# PIN2DMD_PWR.net
KiCad netlist of a schematic drawn in EAGLE
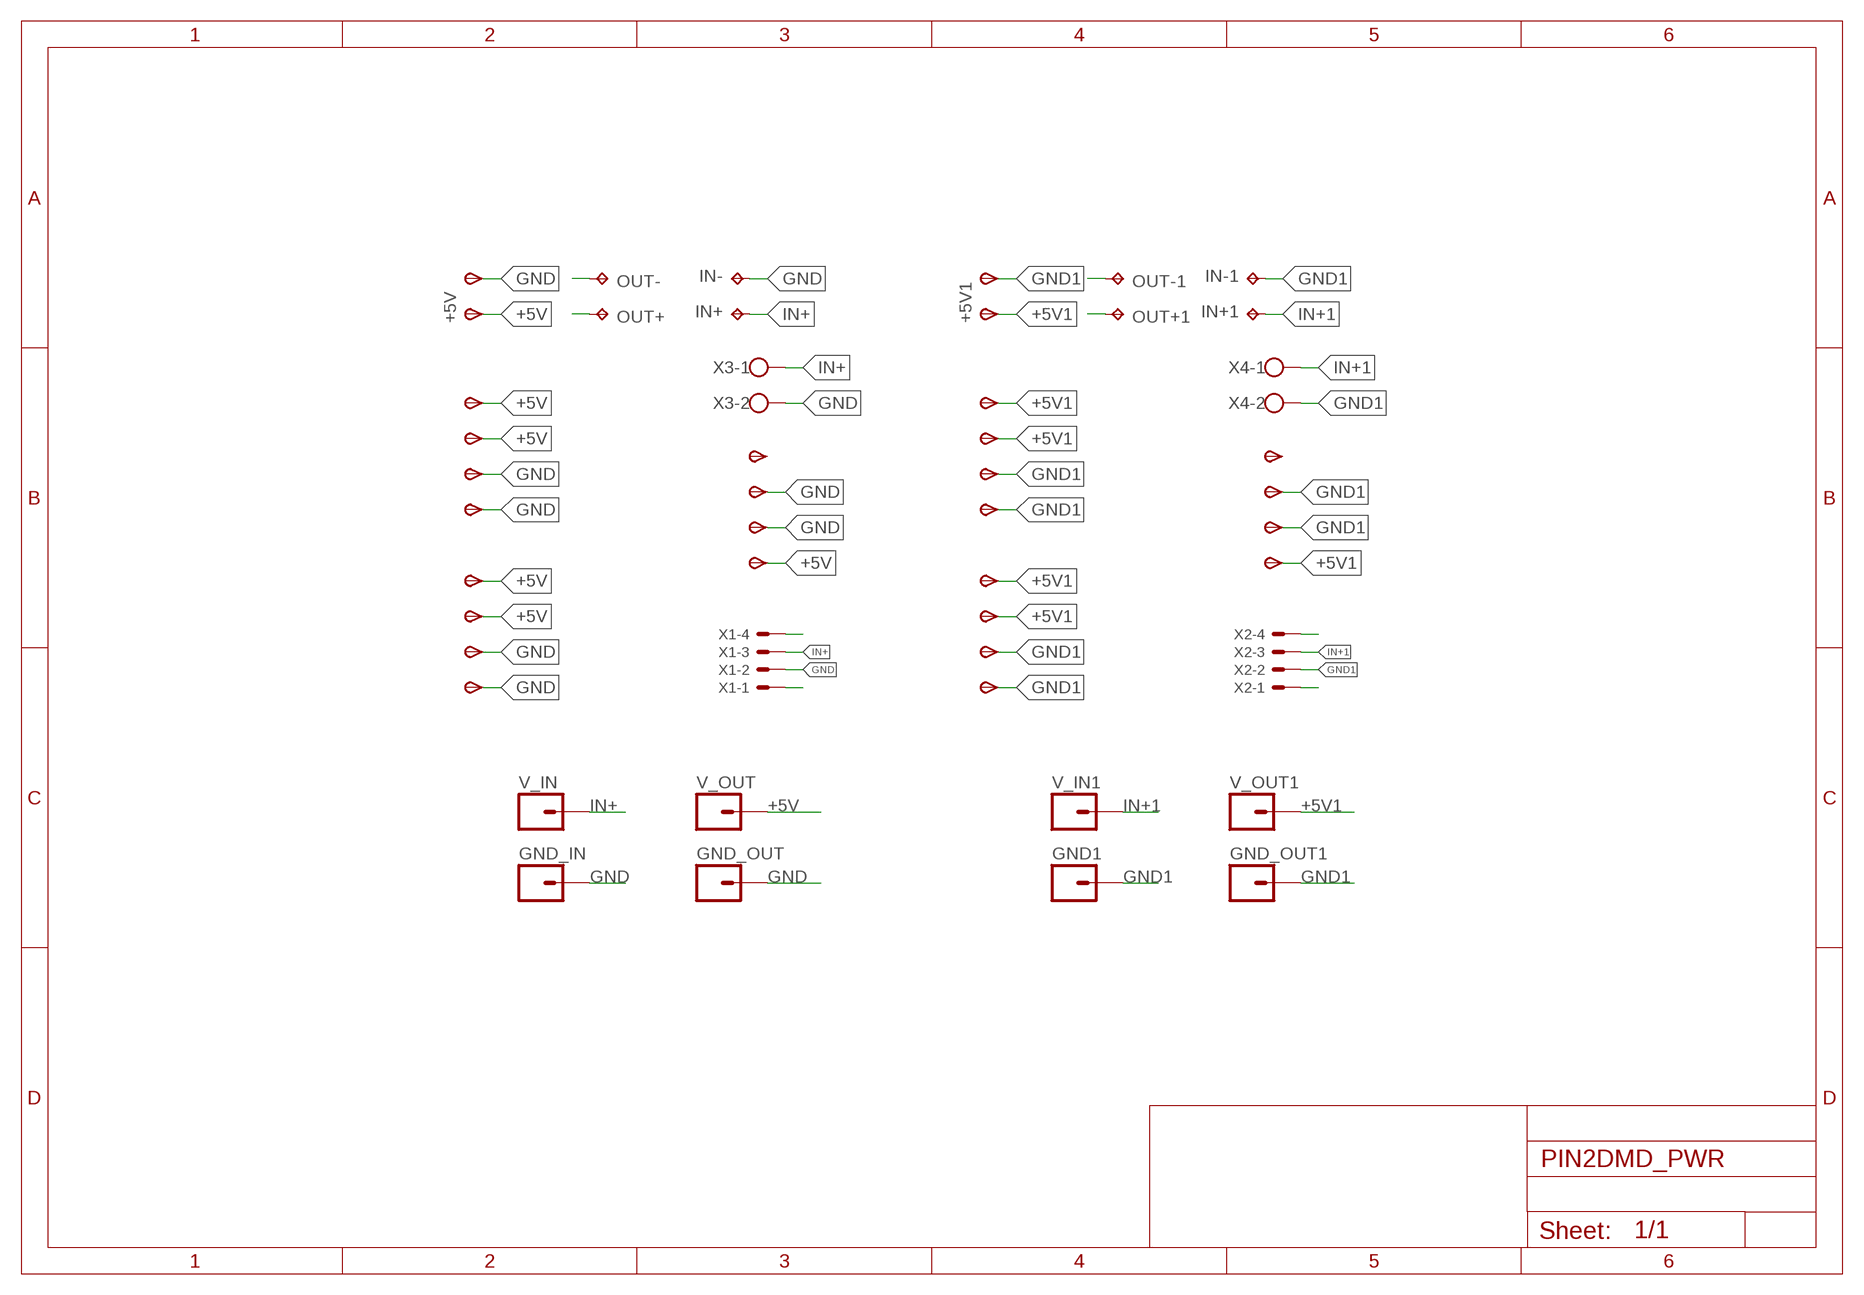
[diagram p0: schematic, sheet 1]

(export (version "E")
  (design (tool "Eeschema 10.0.6"))
  (components
    (comp (ref "+5V")
      (value "TPSPAD1-20Y")
      (footprint "eagle-import:P1-20Y")
      (libsource (lib "eagle-import") (part "TPSPAD1-20Y"))
    )
    (comp (ref "+5V1")
      (value "TPSPAD1-20Y")
      (footprint "eagle-import:P1-20Y")
      (libsource (lib "eagle-import") (part "TPSPAD1-20Y"))
    )
    (comp (ref "GND1")
      (value "M01PTH")
      (footprint "eagle-import:1X01")
      (libsource (lib "eagle-import") (part "M01PTH"))
    )
    (comp (ref "GND_IN")
      (value "M01PTH")
      (footprint "eagle-import:1X01")
      (libsource (lib "eagle-import") (part "M01PTH"))
    )
    (comp (ref "GND_OUT")
      (value "M01PTH")
      (footprint "eagle-import:1X01")
      (libsource (lib "eagle-import") (part "M01PTH"))
    )
    (comp (ref "GND_OUT1")
      (value "M01PTH")
      (footprint "eagle-import:1X01")
      (libsource (lib "eagle-import") (part "M01PTH"))
    )
    (comp (ref "IN+")
      (value "TPPAD1-20")
      (footprint "eagle-import:P1-20")
      (libsource (lib "eagle-import") (part "TPPAD1-20"))
    )
    (comp (ref "IN+1")
      (value "TPPAD1-20")
      (footprint "eagle-import:P1-20")
      (libsource (lib "eagle-import") (part "TPPAD1-20"))
    )
    (comp (ref "IN-")
      (value "TPPAD1-20")
      (footprint "eagle-import:P1-20")
      (libsource (lib "eagle-import") (part "TPPAD1-20"))
    )
    (comp (ref "IN-1")
      (value "TPPAD1-20")
      (footprint "eagle-import:P1-20")
      (libsource (lib "eagle-import") (part "TPPAD1-20"))
    )
    (comp (ref "OUT+")
      (value "TPPAD1-20")
      (footprint "eagle-import:P1-20")
      (libsource (lib "eagle-import") (part "TPPAD1-20"))
    )
    (comp (ref "OUT+1")
      (value "TPPAD1-20")
      (footprint "eagle-import:P1-20")
      (libsource (lib "eagle-import") (part "TPPAD1-20"))
    )
    (comp (ref "OUT-")
      (value "TPPAD1-20")
      (footprint "eagle-import:P1-20")
      (libsource (lib "eagle-import") (part "TPPAD1-20"))
    )
    (comp (ref "OUT-1")
      (value "TPPAD1-20")
      (footprint "eagle-import:P1-20")
      (libsource (lib "eagle-import") (part "TPPAD1-20"))
    )
    (comp (ref "TP1")
      (value "TPSPAD1-20Y")
      (footprint "eagle-import:P1-20Y")
      (libsource (lib "eagle-import") (part "TPSPAD1-20Y"))
    )
    (comp (ref "TP2")
      (value "TPSPAD1-20Y")
      (footprint "eagle-import:P1-20Y")
      (libsource (lib "eagle-import") (part "TPSPAD1-20Y"))
    )
    (comp (ref "TP3")
      (value "TPSPAD1-20Y")
      (footprint "eagle-import:P1-20Y")
      (libsource (lib "eagle-import") (part "TPSPAD1-20Y"))
    )
    (comp (ref "TP4")
      (value "TPSPAD1-20Y")
      (footprint "eagle-import:P1-20Y")
      (libsource (lib "eagle-import") (part "TPSPAD1-20Y"))
    )
    (comp (ref "TP5")
      (value "TPSPAD1-20Y")
      (footprint "eagle-import:P1-20Y")
      (libsource (lib "eagle-import") (part "TPSPAD1-20Y"))
    )
    (comp (ref "TP6")
      (value "TPSPAD1-20Y")
      (footprint "eagle-import:P1-20Y")
      (libsource (lib "eagle-import") (part "TPSPAD1-20Y"))
    )
    (comp (ref "TP7")
      (value "TPSPAD1-20Y")
      (footprint "eagle-import:P1-20Y")
      (libsource (lib "eagle-import") (part "TPSPAD1-20Y"))
    )
    (comp (ref "TP8")
      (value "TPSPAD1-20Y")
      (footprint "eagle-import:P1-20Y")
      (libsource (lib "eagle-import") (part "TPSPAD1-20Y"))
    )
    (comp (ref "TP9")
      (value "TPSPAD1-20Y")
      (footprint "eagle-import:P1-20Y")
      (libsource (lib "eagle-import") (part "TPSPAD1-20Y"))
    )
    (comp (ref "TP10")
      (value "TPSPAD1-20Y")
      (footprint "eagle-import:P1-20Y")
      (libsource (lib "eagle-import") (part "TPSPAD1-20Y"))
    )
    (comp (ref "TP11")
      (value "TPSPAD1-20Y")
      (footprint "eagle-import:P1-20Y")
      (libsource (lib "eagle-import") (part "TPSPAD1-20Y"))
    )
    (comp (ref "TP12")
      (value "TPSPAD1-20Y")
      (footprint "eagle-import:P1-20Y")
      (libsource (lib "eagle-import") (part "TPSPAD1-20Y"))
    )
    (comp (ref "TP13")
      (value "TPSPAD1-20Y")
      (footprint "eagle-import:P1-20Y")
      (libsource (lib "eagle-import") (part "TPSPAD1-20Y"))
    )
    (comp (ref "TP14")
      (value "TPSPAD1-20Y")
      (footprint "eagle-import:P1-20Y")
      (libsource (lib "eagle-import") (part "TPSPAD1-20Y"))
    )
    (comp (ref "TP15")
      (value "TPSPAD1-20Y")
      (footprint "eagle-import:P1-20Y")
      (libsource (lib "eagle-import") (part "TPSPAD1-20Y"))
    )
    (comp (ref "TP16")
      (value "TPSPAD1-20Y")
      (footprint "eagle-import:P1-20Y")
      (libsource (lib "eagle-import") (part "TPSPAD1-20Y"))
    )
    (comp (ref "TP17")
      (value "TPSPAD1-20Y")
      (footprint "eagle-import:P1-20Y")
      (libsource (lib "eagle-import") (part "TPSPAD1-20Y"))
    )
    (comp (ref "TP18")
      (value "TPSPAD1-20Y")
      (footprint "eagle-import:P1-20Y")
      (libsource (lib "eagle-import") (part "TPSPAD1-20Y"))
    )
    (comp (ref "TP19")
      (value "TPSPAD1-20Y")
      (footprint "eagle-import:P1-20Y")
      (libsource (lib "eagle-import") (part "TPSPAD1-20Y"))
    )
    (comp (ref "TP20")
      (value "TPSPAD1-20Y")
      (footprint "eagle-import:P1-20Y")
      (libsource (lib "eagle-import") (part "TPSPAD1-20Y"))
    )
    (comp (ref "TP21")
      (value "TPSPAD1-20Y")
      (footprint "eagle-import:P1-20Y")
      (libsource (lib "eagle-import") (part "TPSPAD1-20Y"))
    )
    (comp (ref "TP22")
      (value "TPSPAD1-20Y")
      (footprint "eagle-import:P1-20Y")
      (libsource (lib "eagle-import") (part "TPSPAD1-20Y"))
    )
    (comp (ref "TP23")
      (value "TPSPAD1-20Y")
      (footprint "eagle-import:P1-20Y")
      (libsource (lib "eagle-import") (part "TPSPAD1-20Y"))
    )
    (comp (ref "TP24")
      (value "TPSPAD1-20Y")
      (footprint "eagle-import:P1-20Y")
      (libsource (lib "eagle-import") (part "TPSPAD1-20Y"))
    )
    (comp (ref "TP25")
      (value "TPSPAD1-20Y")
      (footprint "eagle-import:P1-20Y")
      (libsource (lib "eagle-import") (part "TPSPAD1-20Y"))
    )
    (comp (ref "TP26")
      (value "TPSPAD1-20Y")
      (footprint "eagle-import:P1-20Y")
      (libsource (lib "eagle-import") (part "TPSPAD1-20Y"))
    )
    (comp (ref "V_IN")
      (value "M01PTH")
      (footprint "eagle-import:1X01")
      (libsource (lib "eagle-import") (part "M01PTH"))
    )
    (comp (ref "V_IN1")
      (value "M01PTH")
      (footprint "eagle-import:1X01")
      (libsource (lib "eagle-import") (part "M01PTH"))
    )
    (comp (ref "V_OUT")
      (value "M01PTH")
      (footprint "eagle-import:1X01")
      (libsource (lib "eagle-import") (part "M01PTH"))
    )
    (comp (ref "V_OUT1")
      (value "M01PTH")
      (footprint "eagle-import:1X01")
      (libsource (lib "eagle-import") (part "M01PTH"))
    )
    (comp (ref "X1")
      (value "KK-156-4")
      (footprint "eagle-import:KK-156-4")
      (libsource (lib "eagle-import") (part "KK-156-4"))
    )
    (comp (ref "X2")
      (value "KK-156-4")
      (footprint "eagle-import:KK-156-4")
      (libsource (lib "eagle-import") (part "KK-156-4"))
    )
    (comp (ref "X3")
      (value "W237-102")
      (footprint "eagle-import:W237-102")
      (fields (field (name "MPN") "237-102"))
      (libsource (lib "eagle-import") (part "W237-102"))
    )
    (comp (ref "X4")
      (value "W237-102")
      (footprint "eagle-import:W237-102")
      (fields (field (name "MPN") "237-102"))
      (libsource (lib "eagle-import") (part "W237-102"))
    )
  )
  (nets
    (net (code "1") (name "+5V") (class "Default")
      (node (ref "+5V") (pin "TP") (pinfunction "PP_TP") (pintype "input"))
      (node (ref "OUT+") (pin "TP") (pinfunction "TP_TP") (pintype "input"))
      (node (ref "TP13") (pin "TP") (pinfunction "PP_TP") (pintype "input"))
      (node (ref "TP5") (pin "TP") (pinfunction "PP_TP") (pintype "input"))
      (node (ref "TP6") (pin "TP") (pinfunction "PP_TP") (pintype "input"))
      (node (ref "TP7") (pin "TP") (pinfunction "PP_TP") (pintype "input"))
      (node (ref "TP8") (pin "TP") (pinfunction "PP_TP") (pintype "input"))
      (node (ref "V_OUT") (pin "1") (pinfunction "1_1") (pintype "passive"))
    )
    (net (code "2") (name "+5V1") (class "Default")
      (node (ref "+5V1") (pin "TP") (pinfunction "PP_TP") (pintype "input"))
      (node (ref "OUT+1") (pin "TP") (pinfunction "TP_TP") (pintype "input"))
      (node (ref "TP17") (pin "TP") (pinfunction "PP_TP") (pintype "input"))
      (node (ref "TP18") (pin "TP") (pinfunction "PP_TP") (pintype "input"))
      (node (ref "TP19") (pin "TP") (pinfunction "PP_TP") (pintype "input"))
      (node (ref "TP20") (pin "TP") (pinfunction "PP_TP") (pintype "input"))
      (node (ref "TP26") (pin "TP") (pinfunction "PP_TP") (pintype "input"))
      (node (ref "V_OUT1") (pin "1") (pinfunction "1_1") (pintype "passive"))
    )
    (net (code "3") (name "GND") (class "Default")
      (node (ref "GND_IN") (pin "1") (pinfunction "1_1") (pintype "passive"))
      (node (ref "GND_OUT") (pin "1") (pinfunction "1_1") (pintype "passive"))
      (node (ref "IN-") (pin "TP") (pinfunction "TP_TP") (pintype "input"))
      (node (ref "OUT-") (pin "TP") (pinfunction "TP_TP") (pintype "input"))
      (node (ref "TP1") (pin "TP") (pinfunction "PP_TP") (pintype "input"))
      (node (ref "TP10") (pin "TP") (pinfunction "PP_TP") (pintype "input"))
      (node (ref "TP11") (pin "TP") (pinfunction "PP_TP") (pintype "input"))
      (node (ref "TP12") (pin "TP") (pinfunction "PP_TP") (pintype "input"))
      (node (ref "TP3") (pin "TP") (pinfunction "PP_TP") (pintype "input"))
      (node (ref "TP4") (pin "TP") (pinfunction "PP_TP") (pintype "input"))
      (node (ref "TP9") (pin "TP") (pinfunction "PP_TP") (pintype "input"))
      (node (ref "X1") (pin "2") (pinfunction "S_2") (pintype "passive"))
      (node (ref "X3") (pin "2") (pinfunction "KL_2") (pintype "passive"))
    )
    (net (code "4") (name "GND1") (class "Default")
      (node (ref "GND1") (pin "1") (pinfunction "1_1") (pintype "passive"))
      (node (ref "GND_OUT1") (pin "1") (pinfunction "1_1") (pintype "passive"))
      (node (ref "IN-1") (pin "TP") (pinfunction "TP_TP") (pintype "input"))
      (node (ref "OUT-1") (pin "TP") (pinfunction "TP_TP") (pintype "input"))
      (node (ref "TP14") (pin "TP") (pinfunction "PP_TP") (pintype "input"))
      (node (ref "TP15") (pin "TP") (pinfunction "PP_TP") (pintype "input"))
      (node (ref "TP16") (pin "TP") (pinfunction "PP_TP") (pintype "input"))
      (node (ref "TP21") (pin "TP") (pinfunction "PP_TP") (pintype "input"))
      (node (ref "TP22") (pin "TP") (pinfunction "PP_TP") (pintype "input"))
      (node (ref "TP24") (pin "TP") (pinfunction "PP_TP") (pintype "input"))
      (node (ref "TP25") (pin "TP") (pinfunction "PP_TP") (pintype "input"))
      (node (ref "X2") (pin "2") (pinfunction "S_2") (pintype "passive"))
      (node (ref "X4") (pin "2") (pinfunction "KL_2") (pintype "passive"))
    )
    (net (code "5") (name "IN+") (class "Default")
      (node (ref "IN+") (pin "TP") (pinfunction "TP_TP") (pintype "input"))
      (node (ref "V_IN") (pin "1") (pinfunction "1_1") (pintype "passive"))
      (node (ref "X1") (pin "3") (pinfunction "S_3") (pintype "passive"))
      (node (ref "X3") (pin "1") (pinfunction "KL_1") (pintype "passive"))
    )
    (net (code "6") (name "IN+1") (class "Default")
      (node (ref "IN+1") (pin "TP") (pinfunction "TP_TP") (pintype "input"))
      (node (ref "V_IN1") (pin "1") (pinfunction "1_1") (pintype "passive"))
      (node (ref "X2") (pin "3") (pinfunction "S_3") (pintype "passive"))
      (node (ref "X4") (pin "1") (pinfunction "KL_1") (pintype "passive"))
    )
    (net (code "7") (name "unconnected-(TP2-PP-PadTP)") (class "Default")
      (node (ref "TP2") (pin "TP") (pinfunction "PP_TP") (pintype "input"))
    )
    (net (code "8") (name "unconnected-(TP23-PP-PadTP)") (class "Default")
      (node (ref "TP23") (pin "TP") (pinfunction "PP_TP") (pintype "input"))
    )
    (net (code "9") (name "unconnected-(X1A-S-Pad1)") (class "Default")
      (node (ref "X1") (pin "1") (pinfunction "S_1") (pintype "passive"))
    )
    (net (code "10") (name "unconnected-(X1D-S-Pad4)") (class "Default")
      (node (ref "X1") (pin "4") (pinfunction "S_4") (pintype "passive"))
    )
    (net (code "11") (name "unconnected-(X2A-S-Pad1)") (class "Default")
      (node (ref "X2") (pin "1") (pinfunction "S_1") (pintype "passive"))
    )
    (net (code "12") (name "unconnected-(X2D-S-Pad4)") (class "Default")
      (node (ref "X2") (pin "4") (pinfunction "S_4") (pintype "passive"))
    )
  )
)
